# DB3AC_Fldigi_Baofeng_V01.net
KiCad netlist of a schematic drawn in EAGLE
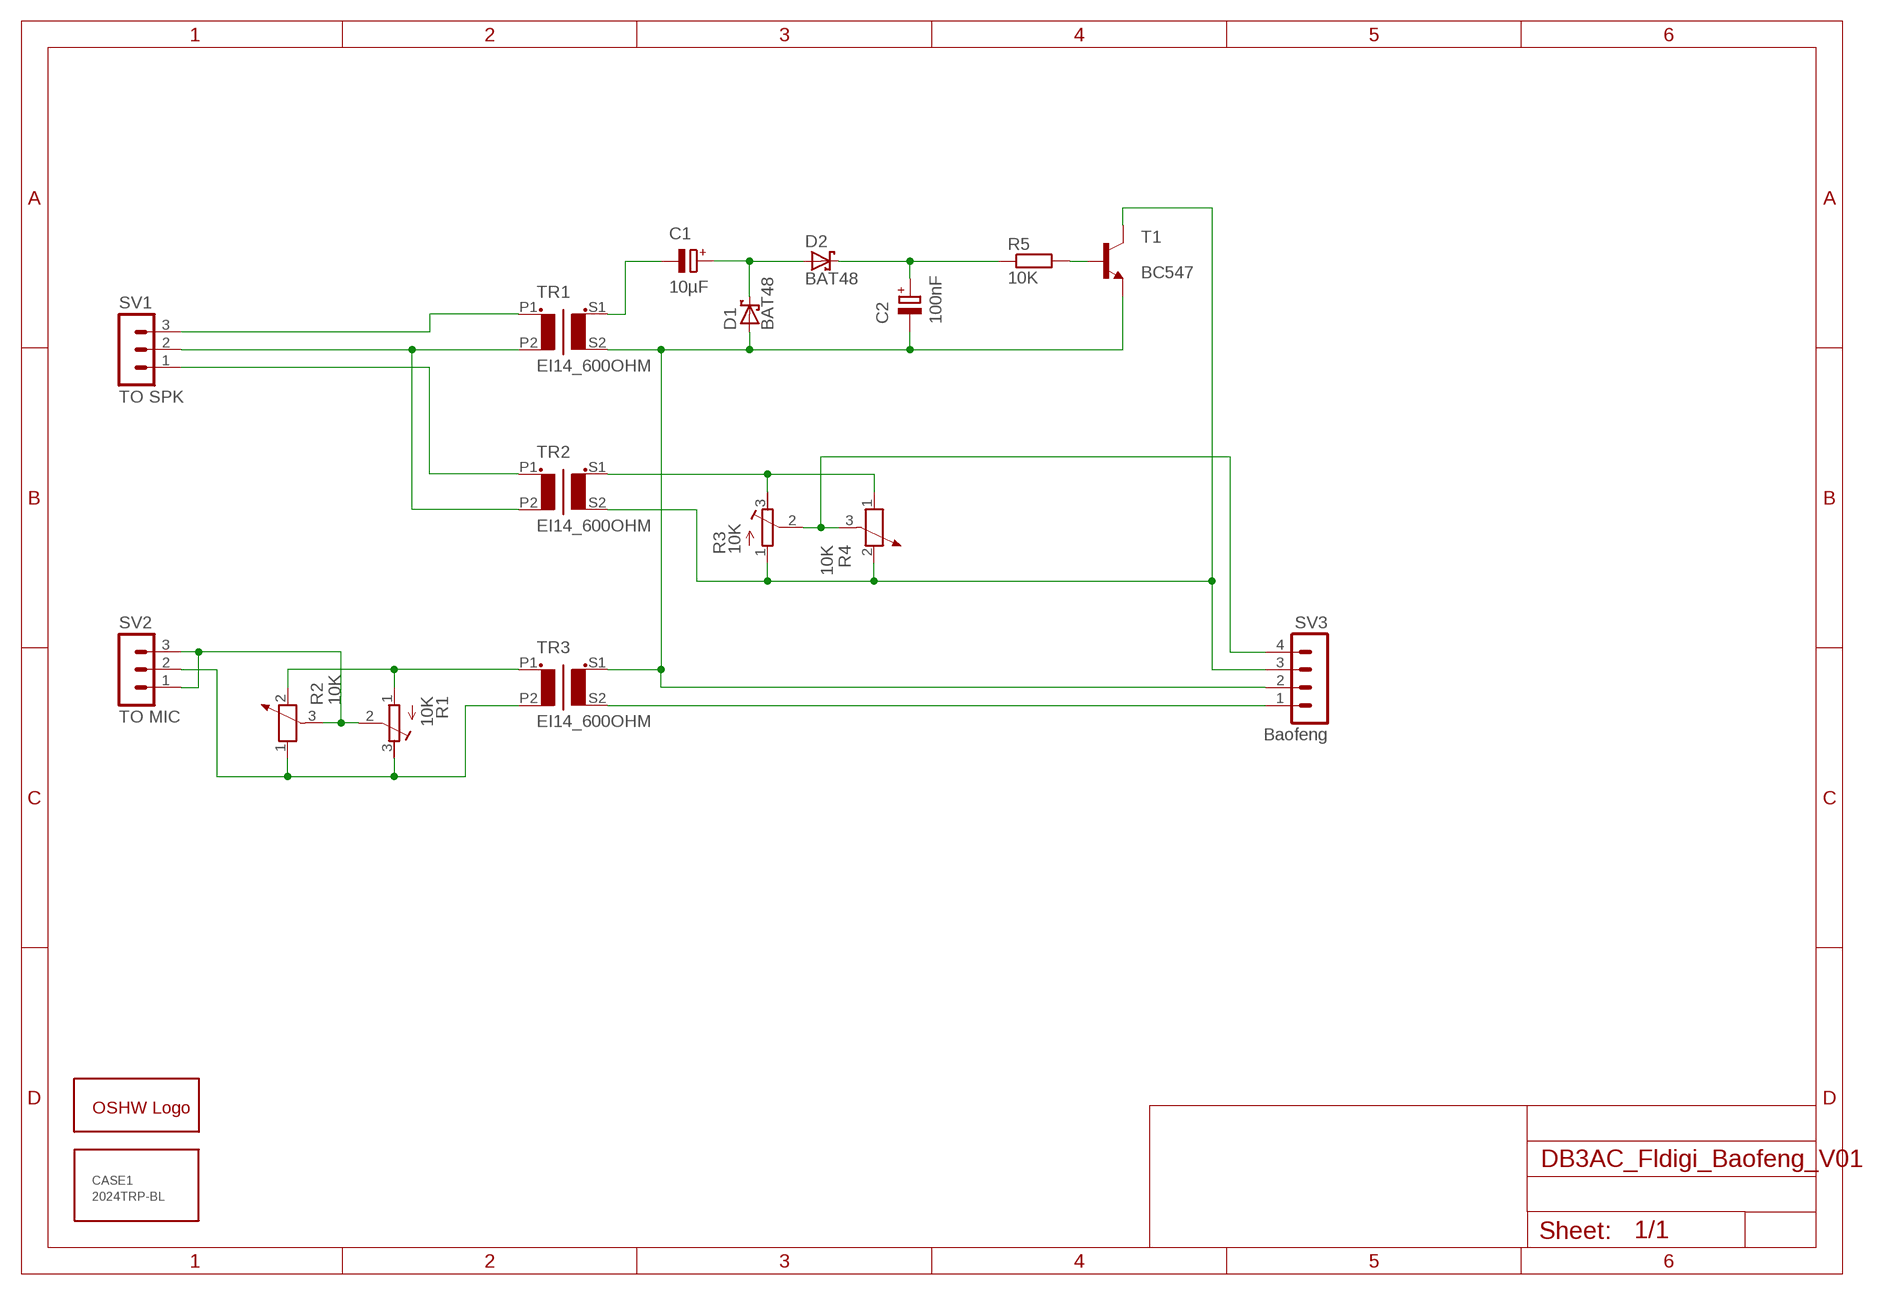
[diagram p0: schematic, sheet 1]

(export (version "E")
  (design (tool "Eeschema 10.0.6"))
  (components
    (comp (ref "C1")
      (value "10µF")
      (footprint "eagle-import:E2,5-7")
      (libsource (lib "eagle-import") (part "CPOL-EUE2.5-7"))
    )
    (comp (ref "C2")
      (value "100nF")
      (footprint "eagle-import:E2,5-7")
      (libsource (lib "eagle-import") (part "CPOL-EUE2.5-7"))
    )
    (comp (ref "CASE1")
      (value "2024TRP-BL")
      (footprint "eagle-import:2024")
      (libsource (lib "eagle-import") (part "2024TRP-BL"))
    )
    (comp (ref "D1")
      (value "BAT48")
      (footprint "eagle-import:DO35-10")
      (libsource (lib "eagle-import") (part "BAT42"))
    )
    (comp (ref "D2")
      (value "BAT48")
      (footprint "eagle-import:DO35-10")
      (libsource (lib "eagle-import") (part "BAT42"))
    )
    (comp (ref "GOLD_ORB_SM1")
      (value "OSHWLOGOLOGO8MM")
      (footprint "eagle-import:OSHW_8MM")
      (libsource (lib "eagle-import") (part "OSHWLOGOLOGO8MM"))
    )
    (comp (ref "R1")
      (value "10K")
      (footprint "eagle-import:RTRIM3339P")
      (libsource (lib "eagle-import") (part "R-TRIMM3339P"))
    )
    (comp (ref "R2")
      (value "10K")
      (footprint "eagle-import:PT-10")
      (libsource (lib "eagle-import") (part "POTENTIOMETER_PT-10"))
    )
    (comp (ref "R3")
      (value "10K")
      (footprint "eagle-import:RTRIM3339P")
      (libsource (lib "eagle-import") (part "R-TRIMM3339P"))
    )
    (comp (ref "R4")
      (value "10K")
      (footprint "eagle-import:PT-10")
      (libsource (lib "eagle-import") (part "POTENTIOMETER_PT-10"))
    )
    (comp (ref "R5")
      (value "10K")
      (footprint "eagle-import:0204_7")
      (libsource (lib "eagle-import") (part "R-EU_0204/7"))
    )
    (comp (ref "SV1")
      (value "TO SPK")
      (footprint "eagle-import:MA03-1")
      (libsource (lib "eagle-import") (part "MA03-1"))
    )
    (comp (ref "SV2")
      (value "TO MIC")
      (footprint "eagle-import:MA03-1")
      (libsource (lib "eagle-import") (part "MA03-1"))
    )
    (comp (ref "SV3")
      (value "Baofeng")
      (footprint "eagle-import:MA04-1")
      (libsource (lib "eagle-import") (part "MA04-1"))
    )
    (comp (ref "T1")
      (value "BC547")
      (footprint "eagle-import:TO92-CBE")
      (libsource (lib "eagle-import") (part "-NPN-TO92-CBEBC547"))
    )
    (comp (ref "TR1")
      (value "EI14_600OHM")
      (footprint "eagle-import:EI14")
      (libsource (lib "eagle-import") (part "EI14_600OHM"))
    )
    (comp (ref "TR2")
      (value "EI14_600OHM")
      (footprint "eagle-import:EI14")
      (libsource (lib "eagle-import") (part "EI14_600OHM"))
    )
    (comp (ref "TR3")
      (value "EI14_600OHM")
      (footprint "eagle-import:EI14")
      (libsource (lib "eagle-import") (part "EI14_600OHM"))
    )
  )
  (nets
    (net (code "1") (name "Net-(C1-Pad+)") (class "Default")
      (node (ref "C1") (pin "+") (pinfunction "+_+") (pintype "passive"))
      (node (ref "D1") (pin "C") (pinfunction "C_C") (pintype "passive"))
      (node (ref "D2") (pin "A") (pinfunction "A_A") (pintype "passive"))
    )
    (net (code "2") (name "Net-(C1-Pad-)") (class "Default")
      (node (ref "C1") (pin "-") (pinfunction "-_-") (pintype "passive"))
      (node (ref "TR1") (pin "S1") (pinfunction "S1_S1") (pintype "passive"))
    )
    (net (code "3") (name "Net-(C2-Pad+)") (class "Default")
      (node (ref "C2") (pin "+") (pinfunction "+_+") (pintype "passive"))
      (node (ref "D2") (pin "C") (pinfunction "C_C") (pintype "passive"))
      (node (ref "R5") (pin "1") (pinfunction "1_1") (pintype "passive"))
    )
    (net (code "4") (name "Net-(C2-Pad-)") (class "Default")
      (node (ref "C2") (pin "-") (pinfunction "-_-") (pintype "passive"))
      (node (ref "D1") (pin "A") (pinfunction "A_A") (pintype "passive"))
      (node (ref "SV3") (pin "2") (pinfunction "2_2") (pintype "passive"))
      (node (ref "T1") (pin "E") (pinfunction "E_E") (pintype "passive"))
      (node (ref "TR1") (pin "S2") (pinfunction "S2_S2") (pintype "passive"))
      (node (ref "TR3") (pin "S1") (pinfunction "S1_S1") (pintype "passive"))
    )
    (net (code "5") (name "Net-(R1-A)") (class "Default")
      (node (ref "R1") (pin "1") (pinfunction "A_1") (pintype "passive"))
      (node (ref "R2") (pin "2") (pinfunction "2_2") (pintype "passive"))
      (node (ref "TR3") (pin "P1") (pinfunction "P1_P1") (pintype "passive"))
    )
    (net (code "6") (name "Net-(R1-E)") (class "Default")
      (node (ref "R1") (pin "3") (pinfunction "E_3") (pintype "passive"))
      (node (ref "R2") (pin "1") (pinfunction "1_1") (pintype "passive"))
      (node (ref "SV2") (pin "2") (pinfunction "2_2") (pintype "passive"))
      (node (ref "TR3") (pin "P2") (pinfunction "P2_P2") (pintype "passive"))
    )
    (net (code "7") (name "Net-(R1-S)") (class "Default")
      (node (ref "R1") (pin "2") (pinfunction "S_2") (pintype "passive"))
      (node (ref "R2") (pin "3") (pinfunction "3_3") (pintype "passive"))
      (node (ref "SV2") (pin "1") (pinfunction "1_1") (pintype "passive"))
      (node (ref "SV2") (pin "3") (pinfunction "3_3") (pintype "passive"))
    )
    (net (code "8") (name "Net-(R3-A)") (class "Default")
      (node (ref "R3") (pin "1") (pinfunction "A_1") (pintype "passive"))
      (node (ref "R4") (pin "2") (pinfunction "2_2") (pintype "passive"))
      (node (ref "SV3") (pin "3") (pinfunction "3_3") (pintype "passive"))
      (node (ref "T1") (pin "C") (pinfunction "C_C") (pintype "passive"))
      (node (ref "TR2") (pin "S2") (pinfunction "S2_S2") (pintype "passive"))
    )
    (net (code "9") (name "Net-(R3-E)") (class "Default")
      (node (ref "R3") (pin "3") (pinfunction "E_3") (pintype "passive"))
      (node (ref "R4") (pin "1") (pinfunction "1_1") (pintype "passive"))
      (node (ref "TR2") (pin "S1") (pinfunction "S1_S1") (pintype "passive"))
    )
    (net (code "10") (name "Net-(R3-S)") (class "Default")
      (node (ref "R3") (pin "2") (pinfunction "S_2") (pintype "passive"))
      (node (ref "R4") (pin "3") (pinfunction "3_3") (pintype "passive"))
      (node (ref "SV3") (pin "4") (pinfunction "4_4") (pintype "passive"))
    )
    (net (code "11") (name "Net-(R5-Pad2)") (class "Default")
      (node (ref "R5") (pin "2") (pinfunction "2_2") (pintype "passive"))
      (node (ref "T1") (pin "B") (pinfunction "B_B") (pintype "passive"))
    )
    (net (code "12") (name "Net-(SV1-Pad1)") (class "Default")
      (node (ref "SV1") (pin "1") (pinfunction "1_1") (pintype "passive"))
      (node (ref "TR2") (pin "P1") (pinfunction "P1_P1") (pintype "passive"))
    )
    (net (code "13") (name "Net-(SV1-Pad2)") (class "Default")
      (node (ref "SV1") (pin "2") (pinfunction "2_2") (pintype "passive"))
      (node (ref "TR1") (pin "P2") (pinfunction "P2_P2") (pintype "passive"))
      (node (ref "TR2") (pin "P2") (pinfunction "P2_P2") (pintype "passive"))
    )
    (net (code "14") (name "Net-(SV1-Pad3)") (class "Default")
      (node (ref "SV1") (pin "3") (pinfunction "3_3") (pintype "passive"))
      (node (ref "TR1") (pin "P1") (pinfunction "P1_P1") (pintype "passive"))
    )
    (net (code "15") (name "Net-(SV3-Pad1)") (class "Default")
      (node (ref "SV3") (pin "1") (pinfunction "1_1") (pintype "passive"))
      (node (ref "TR3") (pin "S2") (pinfunction "S2_S2") (pintype "passive"))
    )
  )
)
